# Top_Level.net
KiCad netlist of a schematic drawn in Altium Designer
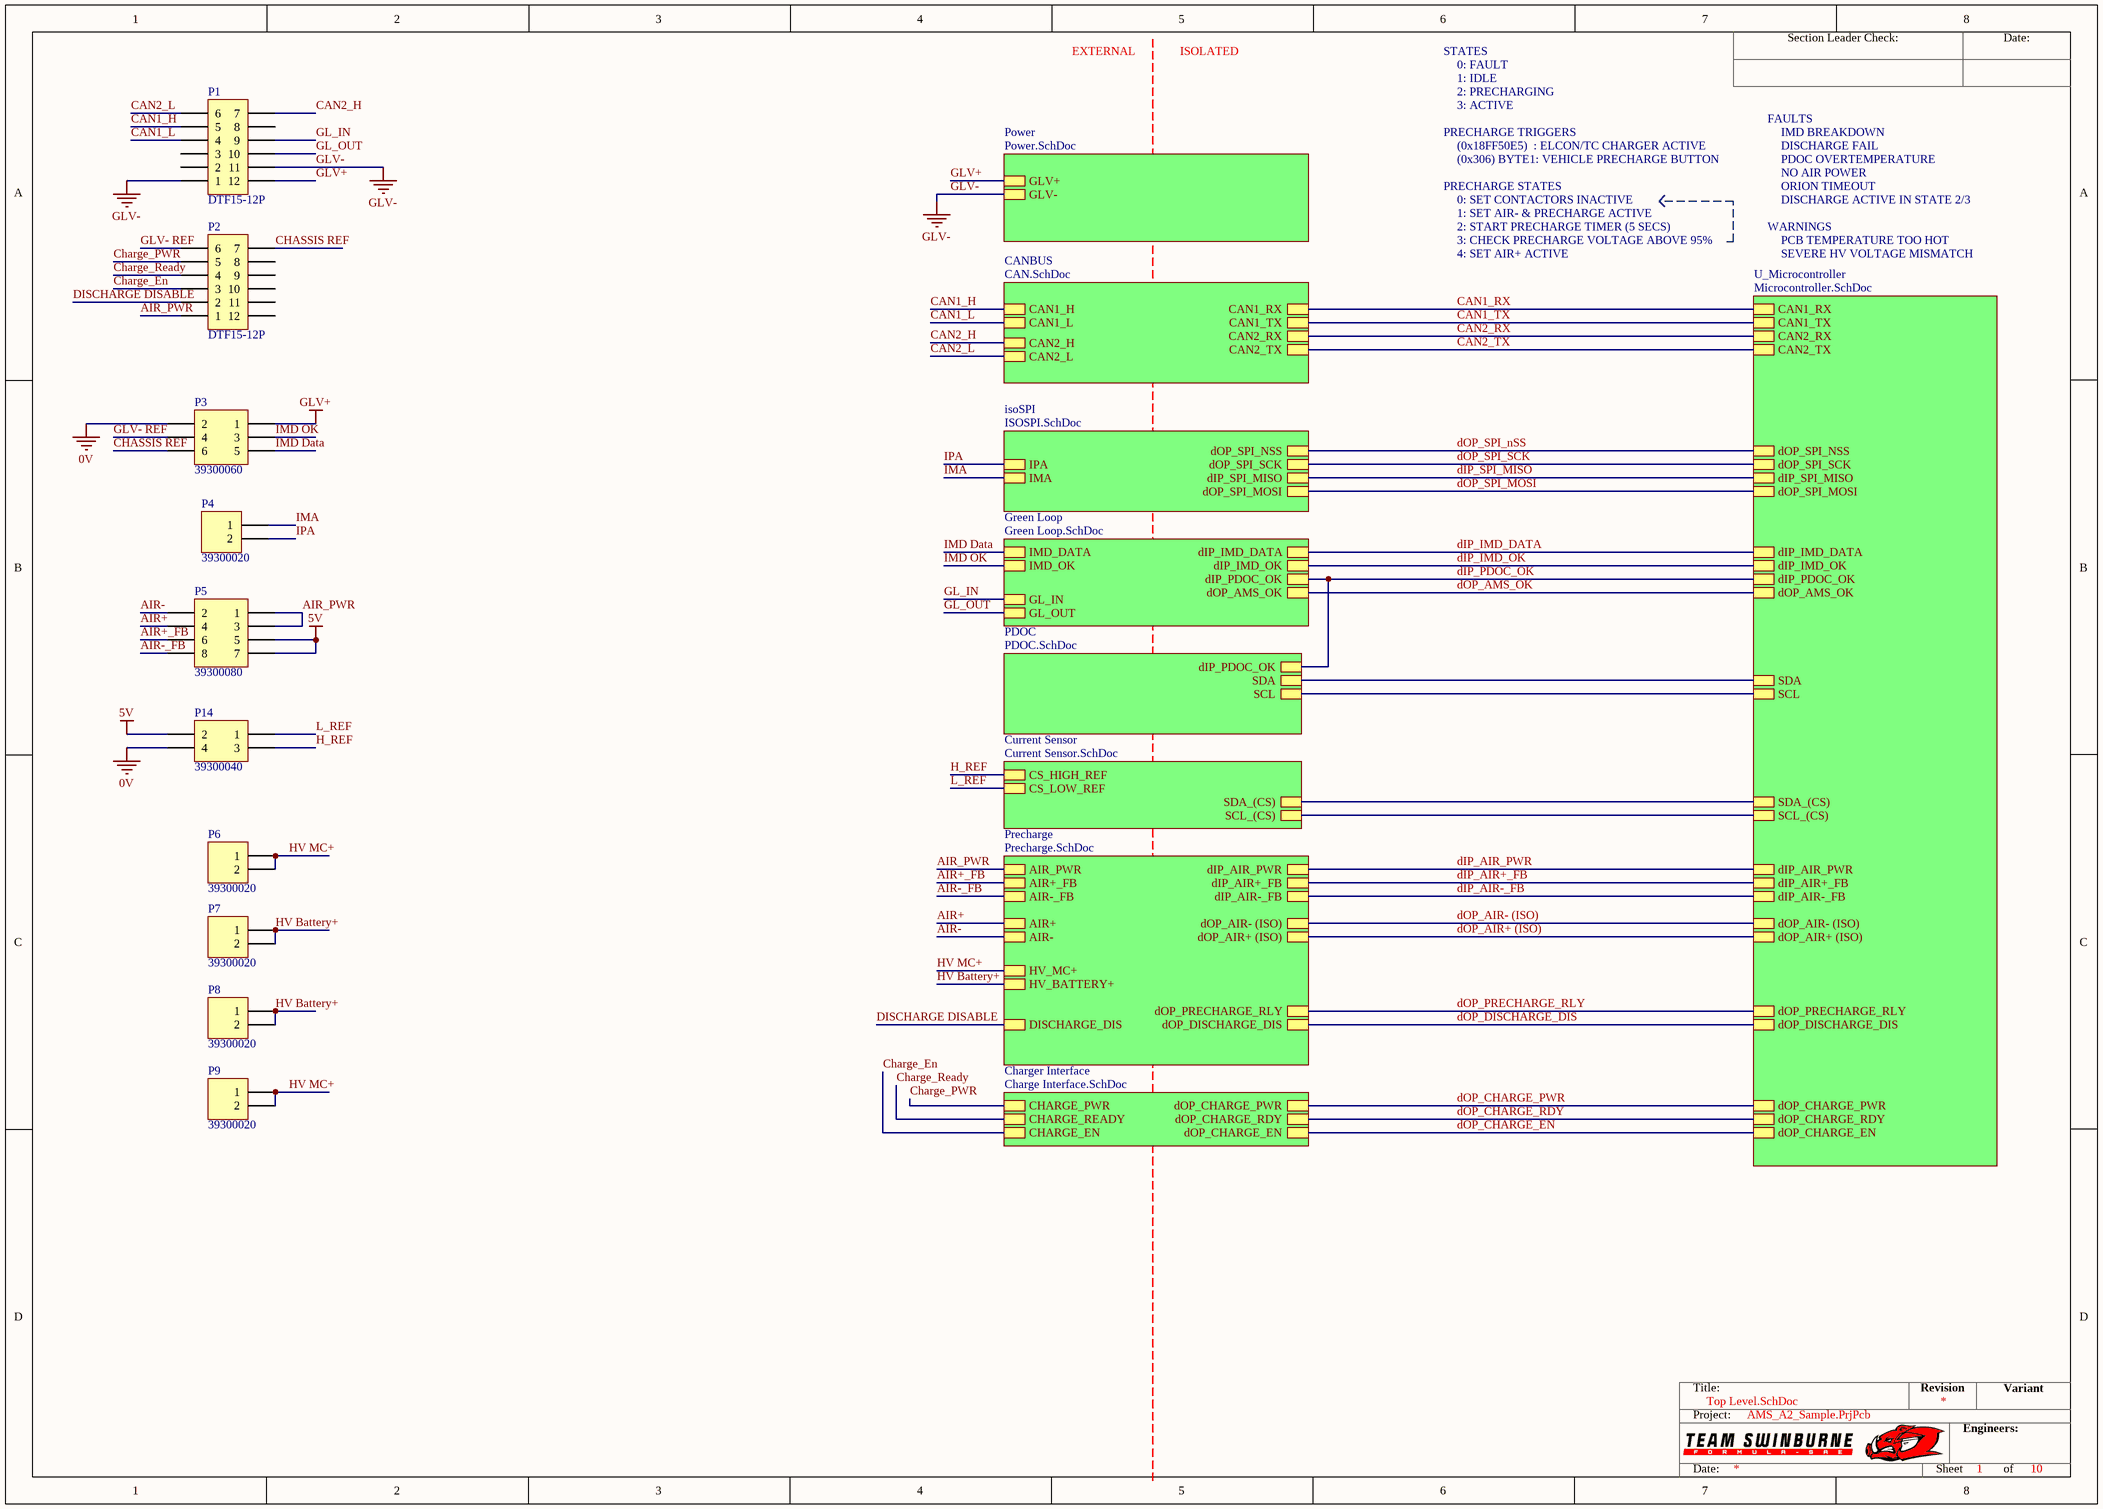
[diagram p0: Top Level.SchDoc]

(export (version "E")
  (design (tool "Eeschema 10.0.6"))
  (components
    (comp (ref "P1")
      (value "DTF15-12P")
      (footprint "DTF15-12P")
      (fields (field (name "DIGIKEY PART NUMBER") "1734-1647-ND") (field (name "CONTACT") "Copper Alloy"))
      (libsource (lib "ts_standard_connectors") (part "DT15-12P"))
    )
    (comp (ref "P2")
      (value "DTF15-12P")
      (footprint "DTF15-12P")
      (fields (field (name "DIGIKEY PART NUMBER") "1734-1647-ND") (field (name "CONTACT") "Copper Alloy"))
      (libsource (lib "ts_standard_connectors") (part "DT15-12P"))
    )
    (comp (ref "P3")
      (value "39300060")
      (footprint "39300060")
      (fields (field (name "DIGIKEY PART NUMBER") "WM21353-ND") (field (name "CONTACT") "Tin"))
      (libsource (lib "ts_standard_connectors") (part "6"))
    )
    (comp (ref "P4")
      (value "39300020")
      (footprint "39300020")
      (fields (field (name "DIGIKEY PART NUMBER") "WM21351-ND") (field (name "CONTACT") "Tin"))
      (libsource (lib "ts_standard_connectors") (part "2"))
    )
    (comp (ref "P5")
      (value "39300080")
      (footprint "39300080")
      (fields (field (name "DIGIKEY PART NUMBER") "WM21354-ND") (field (name "CONTACT") "Tin"))
      (libsource (lib "ts_standard_connectors") (part "8"))
    )
    (comp (ref "P6")
      (value "39300020")
      (footprint "39300020")
      (fields (field (name "DIGIKEY PART NUMBER") "WM21351-ND") (field (name "CONTACT") "Tin"))
      (libsource (lib "ts_standard_connectors") (part "2"))
    )
    (comp (ref "P7")
      (value "39300020")
      (footprint "39300020")
      (fields (field (name "DIGIKEY PART NUMBER") "WM21351-ND") (field (name "CONTACT") "Tin"))
      (libsource (lib "ts_standard_connectors") (part "2"))
    )
    (comp (ref "P8")
      (value "39300020")
      (footprint "39300020")
      (fields (field (name "DIGIKEY PART NUMBER") "WM21351-ND") (field (name "CONTACT") "Tin"))
      (libsource (lib "ts_standard_connectors") (part "2"))
    )
    (comp (ref "P9")
      (value "39300020")
      (footprint "39300020")
      (fields (field (name "DIGIKEY PART NUMBER") "WM21351-ND") (field (name "CONTACT") "Tin"))
      (libsource (lib "ts_standard_connectors") (part "2"))
    )
    (comp (ref "P14")
      (value "39300040")
      (footprint "39300040")
      (fields (field (name "DIGIKEY PART NUMBER") "WM21352-ND") (field (name "CONTACT") "Tin"))
      (libsource (lib "ts_standard_connectors") (part "4"))
    )
  )
  (nets
    (net (code "1") (name "/AIR+") (class "Default")
      (node (ref "P5") (pin "4") (pinfunction "4_4") (pintype "passive"))
    )
    (net (code "2") (name "/AIR+_FB") (class "Default")
      (node (ref "P5") (pin "6") (pinfunction "6_6") (pintype "passive"))
    )
    (net (code "3") (name "/AIR-") (class "Default")
      (node (ref "P5") (pin "2") (pinfunction "2_2") (pintype "passive"))
    )
    (net (code "4") (name "/AIR-_FB") (class "Default")
      (node (ref "P5") (pin "8") (pinfunction "8_8") (pintype "passive"))
    )
    (net (code "5") (name "/AIR_PWR") (class "Default")
      (node (ref "P2") (pin "1") (pinfunction "1_1") (pintype "power_in"))
      (node (ref "P5") (pin "1") (pinfunction "1_1") (pintype "passive"))
      (node (ref "P5") (pin "3") (pinfunction "3_3") (pintype "passive"))
    )
    (net (code "6") (name "/CAN1_H") (class "Default")
      (node (ref "P1") (pin "5") (pinfunction "5_5") (pintype "power_in"))
    )
    (net (code "7") (name "/CAN1_L") (class "Default")
      (node (ref "P1") (pin "4") (pinfunction "4_4") (pintype "power_in"))
    )
    (net (code "10") (name "/CAN2_H") (class "Default")
      (node (ref "P1") (pin "7") (pinfunction "7_7") (pintype "passive"))
    )
    (net (code "11") (name "/CAN2_L") (class "Default")
      (node (ref "P1") (pin "6") (pinfunction "6_6") (pintype "power_in"))
    )
    (net (code "14") (name "/CHASSIS REF") (class "Default")
      (node (ref "P2") (pin "7") (pinfunction "7_7") (pintype "passive"))
      (node (ref "P3") (pin "6") (pinfunction "6_6") (pintype "passive"))
    )
    (net (code "15") (name "/Charge_En") (class "Default")
      (node (ref "P2") (pin "3") (pinfunction "3_3") (pintype "power_in"))
    )
    (net (code "16") (name "/Charge_PWR") (class "Default")
      (node (ref "P2") (pin "5") (pinfunction "5_5") (pintype "power_in"))
    )
    (net (code "17") (name "/Charge_Ready") (class "Default")
      (node (ref "P2") (pin "4") (pinfunction "4_4") (pintype "power_in"))
    )
    (net (code "18") (name "/DISCHARGE DISABLE") (class "Default")
      (node (ref "P2") (pin "2") (pinfunction "2_2") (pintype "power_in"))
    )
    (net (code "19") (name "/GLV- REF") (class "Default")
      (node (ref "P2") (pin "6") (pinfunction "6_6") (pintype "power_in"))
      (node (ref "P3") (pin "4") (pinfunction "4_4") (pintype "passive"))
    )
    (net (code "20") (name "/GL_IN") (class "Default")
      (node (ref "P1") (pin "9") (pinfunction "9_9") (pintype "passive"))
    )
    (net (code "21") (name "/GL_OUT") (class "Default")
      (node (ref "P1") (pin "10") (pinfunction "10_10") (pintype "passive"))
    )
    (net (code "22") (name "/HV Battery+") (class "Default")
      (node (ref "P7") (pin "1") (pinfunction "1_1") (pintype "passive"))
      (node (ref "P7") (pin "2") (pinfunction "2_2") (pintype "passive"))
      (node (ref "P8") (pin "1") (pinfunction "1_1") (pintype "passive"))
      (node (ref "P8") (pin "2") (pinfunction "2_2") (pintype "passive"))
    )
    (net (code "23") (name "/HV MC+") (class "Default")
      (node (ref "P6") (pin "1") (pinfunction "1_1") (pintype "passive"))
      (node (ref "P6") (pin "2") (pinfunction "2_2") (pintype "passive"))
      (node (ref "P9") (pin "1") (pinfunction "1_1") (pintype "passive"))
      (node (ref "P9") (pin "2") (pinfunction "2_2") (pintype "passive"))
    )
    (net (code "24") (name "/H_REF") (class "Default")
      (node (ref "P14") (pin "3") (pinfunction "3_3") (pintype "passive"))
    )
    (net (code "25") (name "/IMA") (class "Default")
      (node (ref "P4") (pin "1") (pinfunction "1_1") (pintype "passive"))
    )
    (net (code "26") (name "/IMD Data") (class "Default")
      (node (ref "P3") (pin "5") (pinfunction "5_5") (pintype "passive"))
    )
    (net (code "27") (name "/IMD OK") (class "Default")
      (node (ref "P3") (pin "3") (pinfunction "3_3") (pintype "passive"))
    )
    (net (code "28") (name "/IPA") (class "Default")
      (node (ref "P4") (pin "2") (pinfunction "2_2") (pintype "passive"))
    )
    (net (code "29") (name "/L_REF") (class "Default")
      (node (ref "P14") (pin "1") (pinfunction "1_1") (pintype "passive"))
    )
    (net (code "52") (name "0V") (class "Default")
      (node (ref "P14") (pin "4") (pinfunction "4_4") (pintype "passive"))
      (node (ref "P3") (pin "2") (pinfunction "2_2") (pintype "passive"))
    )
    (net (code "53") (name "5V") (class "Default")
      (node (ref "P14") (pin "2") (pinfunction "2_2") (pintype "passive"))
      (node (ref "P5") (pin "5") (pinfunction "5_5") (pintype "passive"))
      (node (ref "P5") (pin "7") (pinfunction "7_7") (pintype "passive"))
    )
    (net (code "54") (name "GLV+") (class "Default")
      (node (ref "P1") (pin "12") (pinfunction "12_12") (pintype "passive"))
      (node (ref "P3") (pin "1") (pinfunction "1_1") (pintype "passive"))
    )
    (net (code "55") (name "GLV-") (class "Default")
      (node (ref "P1") (pin "1") (pinfunction "1_1") (pintype "power_in"))
      (node (ref "P1") (pin "11") (pinfunction "11_11") (pintype "passive"))
    )
    (net (code "56") (name "unconnected-(P1-Pad2)") (class "Default")
      (node (ref "P1") (pin "2") (pinfunction "2_2") (pintype "power_in"))
    )
    (net (code "57") (name "unconnected-(P1-Pad3)") (class "Default")
      (node (ref "P1") (pin "3") (pinfunction "3_3") (pintype "power_in"))
    )
    (net (code "58") (name "unconnected-(P1-Pad8)") (class "Default")
      (node (ref "P1") (pin "8") (pinfunction "8_8") (pintype "passive"))
    )
    (net (code "59") (name "unconnected-(P2-Pad8)") (class "Default")
      (node (ref "P2") (pin "8") (pinfunction "8_8") (pintype "passive"))
    )
    (net (code "60") (name "unconnected-(P2-Pad9)") (class "Default")
      (node (ref "P2") (pin "9") (pinfunction "9_9") (pintype "passive"))
    )
    (net (code "61") (name "unconnected-(P2-Pad10)") (class "Default")
      (node (ref "P2") (pin "10") (pinfunction "10_10") (pintype "passive"))
    )
    (net (code "62") (name "unconnected-(P2-Pad11)") (class "Default")
      (node (ref "P2") (pin "11") (pinfunction "11_11") (pintype "passive"))
    )
    (net (code "63") (name "unconnected-(P2-Pad12)") (class "Default")
      (node (ref "P2") (pin "12") (pinfunction "12_12") (pintype "passive"))
    )
  )
)
